# Isolated_Comms_-_AMS.net
KiCad netlist of a schematic drawn in Altium Designer
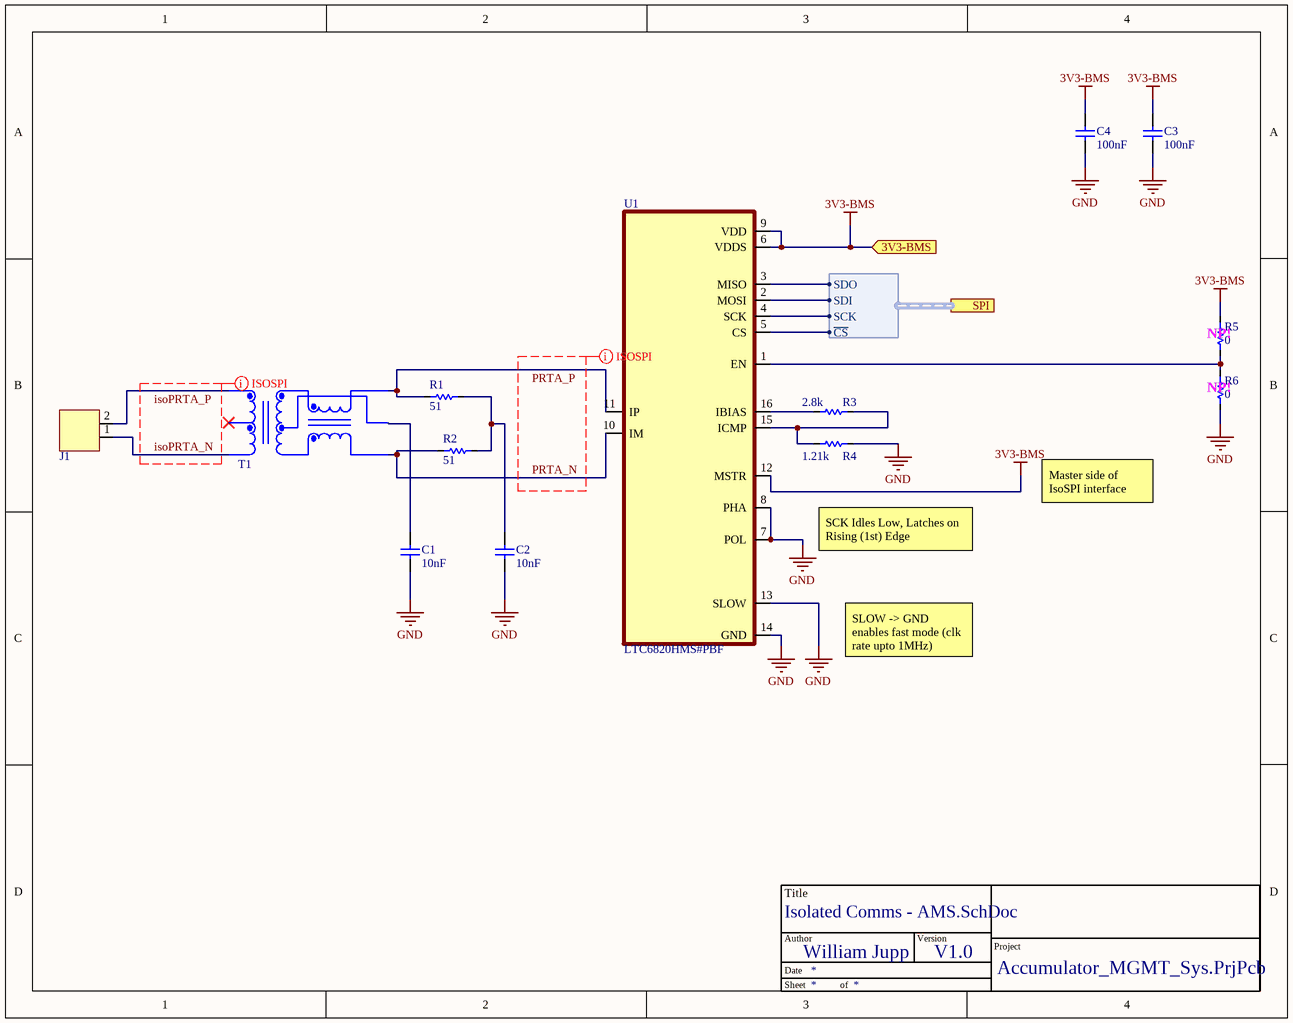
[diagram p0: Isolated Comms - AMS.SchDoc]

(export (version "E")
  (design (tool "Eeschema 10.0.6"))
  (components
    (comp (ref "C1")
      (value "10nF")
      (footprint "C_0603")
      (description "Capacitor")
      (fields (field (name "Comment") "06035C103KAT4A"))
      (libsource (lib "Passives") (part "Capacitor"))
    )
    (comp (ref "C2")
      (value "10nF")
      (footprint "C_0603")
      (description "Capacitor")
      (fields (field (name "Comment") "06035C103KAT4A"))
      (libsource (lib "Passives") (part "Capacitor"))
    )
    (comp (ref "C3")
      (value "100nF")
      (footprint "C_0603")
      (description "Capacitor")
      (fields (field (name "Comment") "C0603C104K3RAC7013"))
      (libsource (lib "Passives") (part "Capacitor"))
    )
    (comp (ref "C4")
      (value "100nF")
      (footprint "C_0603")
      (description "Capacitor")
      (fields (field (name "Comment") "C0603C104K3RAC7013"))
      (libsource (lib "Passives") (part "Capacitor"))
    )
    (comp (ref "J1")
      (value "3-794632-2")
      (footprint "3-794632-2")
      (description "Micro MATE-N-LOK, Rectangular Power Connectors, Header, Plug, Wire-to-Board, 2 Position")
      (libsource (lib "SamacSys") (part "3-794632-2"))
    )
    (comp (ref "R1")
      (value "51")
      (footprint "R-0603")
      (description "Resistor")
      (fields (field (name "Comment") "CRCW060351R0JNEA"))
      (libsource (lib "Passives") (part "Resistor"))
    )
    (comp (ref "R2")
      (value "51")
      (footprint "R-0603")
      (description "Resistor")
      (fields (field (name "Comment") "CRCW060351R0JNEA"))
      (libsource (lib "Passives") (part "Resistor"))
    )
    (comp (ref "R3")
      (value "2.8k")
      (footprint "R-0603")
      (description "Resistor")
      (fields (field (name "Comment") "RC0603FR-072K8L"))
      (libsource (lib "Passives") (part "Resistor"))
    )
    (comp (ref "R4")
      (value "1.21k")
      (footprint "R-0603")
      (description "Resistor")
      (fields (field (name "Comment") "AC0603FR-071K21L"))
      (libsource (lib "Passives") (part "Resistor"))
    )
    (comp (ref "R5")
      (value "0")
      (footprint "R-0603")
      (description "NP")
      (fields (field (name "Comment") "AC0603JR-100RL"))
      (libsource (lib "Passives") (part "Resistor"))
    )
    (comp (ref "R6")
      (value "0")
      (footprint "R-0603")
      (description "NP")
      (fields (field (name "Comment") "AC0603JR-100RL"))
      (libsource (lib "Passives") (part "Resistor"))
    )
    (comp (ref "T1")
      (value "SM91502ALE")
      (footprint "SM91502ALE")
      (description "BMS XFORMER 1-CH 1000V AECQ +125")
      (fields (field (name "MANUFACTURER") "Bourns"))
      (libsource (lib "PCHLib") (part "SM91502ALE"))
    )
    (comp (ref "U1")
      (value "LTC6820HMS#PBF")
      (footprint "MSOP-16_MS")
      (description "IC COMM INTERFACE ISOSPI 16MSOP")
      (fields
        (field (name "MF") "{'manufacturer': u'Analog Devices Inc.'}")
        (field (name "MANUFACTURER") "Analog Devices / Linear Technology")
      )
      (libsource (lib "LTC6820HMS#PBF") (part "LTC6820HMS#PBF"))
    )
  )
  (nets
    (net (code "2") (name "/PRTA_N") (class "Default")
      (node (ref "R2") (pin "1") (pinfunction "1_1") (pintype "passive"))
      (node (ref "T1") (pin "4") (pinfunction "4_4") (pintype "passive"))
      (node (ref "U1") (pin "10") (pinfunction "IM_10") (pintype "passive"))
    )
    (net (code "3") (name "/PRTA_P") (class "Default")
      (node (ref "R1") (pin "1") (pinfunction "1_1") (pintype "passive"))
      (node (ref "T1") (pin "6") (pinfunction "6_6") (pintype "passive"))
      (node (ref "U1") (pin "11") (pinfunction "IP_11") (pintype "passive"))
    )
    (net (code "4") (name "/SCK") (class "Default")
      (node (ref "U1") (pin "4") (pinfunction "SCK_4") (pintype "passive"))
    )
    (net (code "5") (name "/SDI") (class "Default")
      (node (ref "U1") (pin "2") (pinfunction "MOSI_2") (pintype "passive"))
    )
    (net (code "6") (name "/SDO") (class "Default")
      (node (ref "U1") (pin "3") (pinfunction "MISO_3") (pintype "passive"))
    )
    (net (code "7") (name "/isoPRTA_N") (class "Default")
      (node (ref "J1") (pin "1") (pinfunction "1_1") (pintype "passive"))
      (node (ref "T1") (pin "3") (pinfunction "3_3") (pintype "passive"))
    )
    (net (code "8") (name "/isoPRTA_P") (class "Default")
      (node (ref "J1") (pin "2") (pinfunction "2_2") (pintype "passive"))
      (node (ref "T1") (pin "1") (pinfunction "1_1") (pintype "passive"))
    )
    (net (code "10") (name "/~{CS}") (class "Default")
      (node (ref "U1") (pin "5") (pinfunction "CS_5") (pintype "passive"))
    )
    (net (code "11") (name "3V3-BMS") (class "Default")
      (node (ref "C3") (pin "2") (pinfunction "2_2") (pintype "passive"))
      (node (ref "C4") (pin "2") (pinfunction "2_2") (pintype "passive"))
      (node (ref "R5") (pin "2") (pinfunction "2_2") (pintype "passive"))
      (node (ref "U1") (pin "12") (pinfunction "MSTR_12") (pintype "passive"))
      (node (ref "U1") (pin "6") (pinfunction "VDDS_6") (pintype "passive"))
      (node (ref "U1") (pin "9") (pinfunction "VDD_9") (pintype "passive"))
    )
    (net (code "12") (name "GND") (class "Default")
      (node (ref "C1") (pin "1") (pinfunction "1_1") (pintype "passive"))
      (node (ref "C2") (pin "1") (pinfunction "1_1") (pintype "passive"))
      (node (ref "C3") (pin "1") (pinfunction "1_1") (pintype "passive"))
      (node (ref "C4") (pin "1") (pinfunction "1_1") (pintype "passive"))
      (node (ref "R4") (pin "2") (pinfunction "2_2") (pintype "passive"))
      (node (ref "R6") (pin "1") (pinfunction "1_1") (pintype "passive"))
      (node (ref "U1") (pin "13") (pinfunction "SLOW_13") (pintype "passive"))
      (node (ref "U1") (pin "14") (pinfunction "GND_14") (pintype "passive"))
      (node (ref "U1") (pin "7") (pinfunction "POL_7") (pintype "passive"))
      (node (ref "U1") (pin "8") (pinfunction "PHA_8") (pintype "passive"))
    )
    (net (code "13") (name "Net-(C1-Pad2)") (class "Default")
      (node (ref "C1") (pin "2") (pinfunction "2_2") (pintype "passive"))
      (node (ref "T1") (pin "5") (pinfunction "5_5") (pintype "passive"))
    )
    (net (code "14") (name "Net-(C2-Pad2)") (class "Default")
      (node (ref "C2") (pin "2") (pinfunction "2_2") (pintype "passive"))
      (node (ref "R1") (pin "2") (pinfunction "2_2") (pintype "passive"))
      (node (ref "R2") (pin "2") (pinfunction "2_2") (pintype "passive"))
    )
    (net (code "15") (name "Net-(U1-EN)") (class "Default")
      (node (ref "R5") (pin "1") (pinfunction "1_1") (pintype "passive"))
      (node (ref "R6") (pin "2") (pinfunction "2_2") (pintype "passive"))
      (node (ref "U1") (pin "1") (pinfunction "EN_1") (pintype "passive"))
    )
    (net (code "16") (name "Net-(U1-IBIAS)") (class "Default")
      (node (ref "R3") (pin "1") (pinfunction "1_1") (pintype "passive"))
      (node (ref "U1") (pin "16") (pinfunction "IBIAS_16") (pintype "passive"))
    )
    (net (code "17") (name "Net-(U1-ICMP)") (class "Default")
      (node (ref "R3") (pin "2") (pinfunction "2_2") (pintype "passive"))
      (node (ref "R4") (pin "1") (pinfunction "1_1") (pintype "passive"))
      (node (ref "U1") (pin "15") (pinfunction "ICMP_15") (pintype "passive"))
    )
    (net (code "18") (name "unconnected-(T1-Pad2)") (class "Default")
      (node (ref "T1") (pin "2") (pinfunction "2_2") (pintype "passive+no_connect"))
    )
  )
)
